# spi-breakout-v01.net
KiCad netlist of a schematic drawn in EAGLE
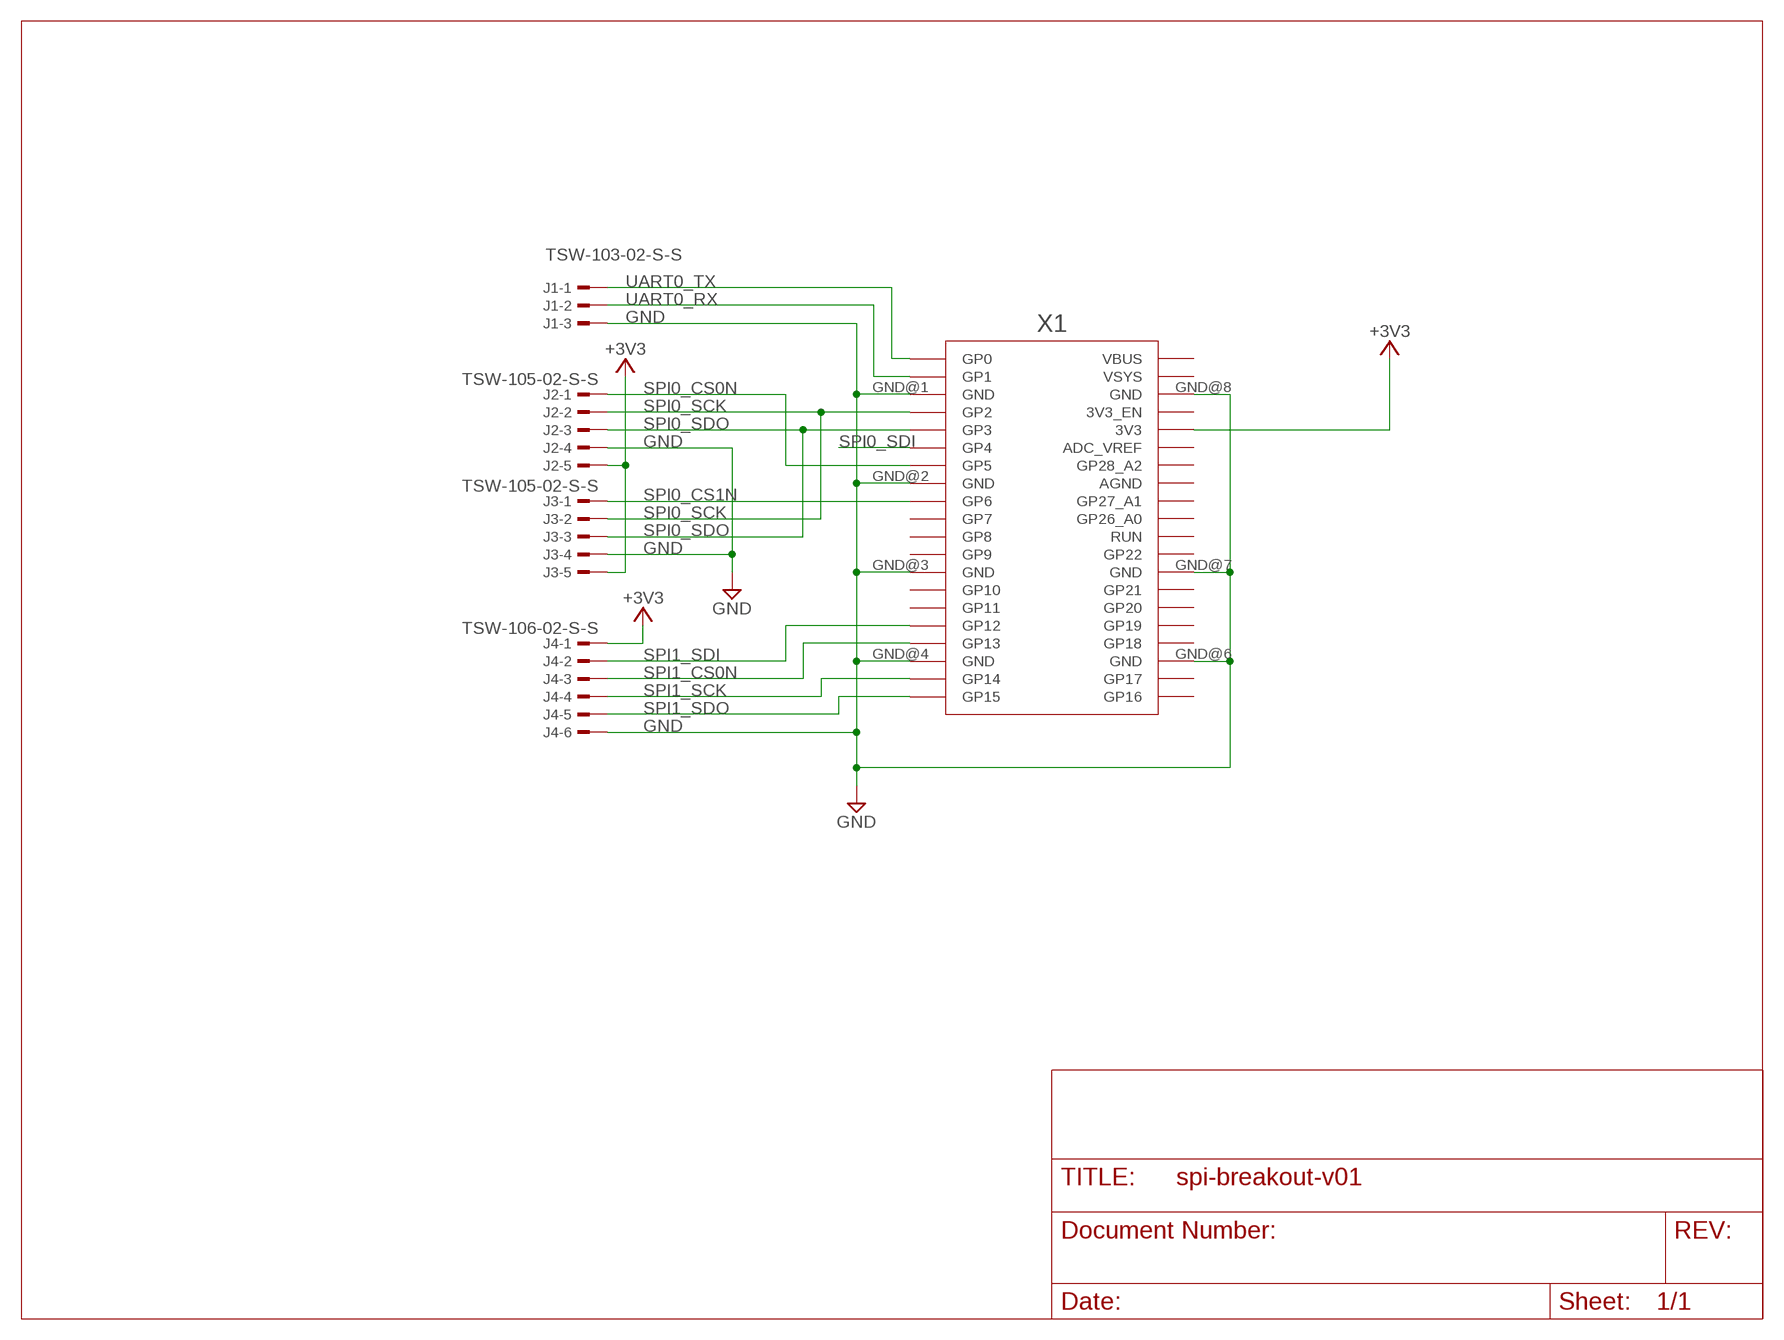
[diagram p0: schematic, sheet 1]

(export (version "E")
  (design (tool "Eeschema 10.0.6"))
  (components
    (comp (ref "J1")
      (value "TSW-103-02-S-S")
      (footprint "eagle-import:TSW-103-02-S-S")
      (libsource (lib "eagle-import") (part "TSW-103-02-S-S"))
    )
    (comp (ref "J2")
      (value "TSW-105-02-S-S")
      (footprint "eagle-import:TSW-105-02-S-S")
      (libsource (lib "eagle-import") (part "TSW-105-02-S-S"))
    )
    (comp (ref "J3")
      (value "TSW-105-02-S-S")
      (footprint "eagle-import:TSW-105-02-S-S")
      (libsource (lib "eagle-import") (part "TSW-105-02-S-S"))
    )
    (comp (ref "J4")
      (value "TSW-106-02-S-S")
      (footprint "eagle-import:TSW-106-02-S-S")
      (libsource (lib "eagle-import") (part "TSW-106-02-S-S"))
    )
    (comp (ref "X1")
      (value "RPI_PICO_IG-TH")
      (footprint "eagle-import:RPI_PICO_TH")
      (libsource (lib "eagle-import") (part "RPI_PICO_IG-TH"))
    )
  )
  (nets
    (net (code "1") (name "+3V3") (class "Default")
      (node (ref "J2") (pin "5") (pinfunction "1_5") (pintype "passive"))
      (node (ref "J3") (pin "5") (pinfunction "1_5") (pintype "passive"))
      (node (ref "J4") (pin "1") (pinfunction "1_1") (pintype "passive"))
      (node (ref "X1") (pin "3V3") (pinfunction "3V3_3V3") (pintype "bidirectional"))
    )
    (net (code "2") (name "/SPI0_CS0N") (class "Default")
      (node (ref "J2") (pin "1") (pinfunction "1_1") (pintype "passive"))
      (node (ref "X1") (pin "GP5") (pinfunction "GP5_GP5") (pintype "bidirectional"))
    )
    (net (code "3") (name "/SPI0_CS1N") (class "Default")
      (node (ref "J3") (pin "1") (pinfunction "1_1") (pintype "passive"))
      (node (ref "X1") (pin "GP6") (pinfunction "GP6_GP6") (pintype "bidirectional"))
    )
    (net (code "4") (name "/SPI0_SCK") (class "Default")
      (node (ref "J2") (pin "2") (pinfunction "1_2") (pintype "passive"))
      (node (ref "J3") (pin "2") (pinfunction "1_2") (pintype "passive"))
      (node (ref "X1") (pin "GP2") (pinfunction "GP2_GP2") (pintype "bidirectional"))
    )
    (net (code "5") (name "/SPI0_SDI") (class "Default")
      (node (ref "X1") (pin "GP4") (pinfunction "GP4_GP4") (pintype "bidirectional"))
    )
    (net (code "6") (name "/SPI0_SDO") (class "Default")
      (node (ref "J2") (pin "3") (pinfunction "1_3") (pintype "passive"))
      (node (ref "J3") (pin "3") (pinfunction "1_3") (pintype "passive"))
      (node (ref "X1") (pin "GP3") (pinfunction "GP3_GP3") (pintype "bidirectional"))
    )
    (net (code "7") (name "/SPI1_CS0N") (class "Default")
      (node (ref "J4") (pin "3") (pinfunction "1_3") (pintype "passive"))
      (node (ref "X1") (pin "GP13") (pinfunction "GP13_GP13") (pintype "bidirectional"))
    )
    (net (code "8") (name "/SPI1_SCK") (class "Default")
      (node (ref "J4") (pin "4") (pinfunction "1_4") (pintype "passive"))
      (node (ref "X1") (pin "GP14") (pinfunction "GP14_GP14") (pintype "bidirectional"))
    )
    (net (code "9") (name "/SPI1_SDI") (class "Default")
      (node (ref "J4") (pin "2") (pinfunction "1_2") (pintype "passive"))
      (node (ref "X1") (pin "GP12") (pinfunction "GP12_GP12") (pintype "bidirectional"))
    )
    (net (code "10") (name "/SPI1_SDO") (class "Default")
      (node (ref "J4") (pin "5") (pinfunction "1_5") (pintype "passive"))
      (node (ref "X1") (pin "GP15") (pinfunction "GP15_GP15") (pintype "bidirectional"))
    )
    (net (code "11") (name "/UART0_RX") (class "Default")
      (node (ref "J1") (pin "2") (pinfunction "1_2") (pintype "passive"))
      (node (ref "X1") (pin "GP1") (pinfunction "GP1_GP1") (pintype "bidirectional"))
    )
    (net (code "12") (name "/UART0_TX") (class "Default")
      (node (ref "J1") (pin "1") (pinfunction "1_1") (pintype "passive"))
      (node (ref "X1") (pin "GP0") (pinfunction "GP0_GP0") (pintype "bidirectional"))
    )
    (net (code "13") (name "GND") (class "Default")
      (node (ref "J1") (pin "3") (pinfunction "1_3") (pintype "passive"))
      (node (ref "J2") (pin "4") (pinfunction "1_4") (pintype "passive"))
      (node (ref "J3") (pin "4") (pinfunction "1_4") (pintype "passive"))
      (node (ref "J4") (pin "6") (pinfunction "1_6") (pintype "passive"))
      (node (ref "X1") (pin "GND@1") (pinfunction "GND_GND@1") (pintype "bidirectional"))
      (node (ref "X1") (pin "GND@2") (pinfunction "GND_GND@2") (pintype "bidirectional"))
      (node (ref "X1") (pin "GND@3") (pinfunction "GND_GND@3") (pintype "bidirectional"))
      (node (ref "X1") (pin "GND@4") (pinfunction "GND_GND@4") (pintype "bidirectional"))
      (node (ref "X1") (pin "GND@6") (pinfunction "GND_GND@6") (pintype "bidirectional"))
      (node (ref "X1") (pin "GND@7") (pinfunction "GND_GND@7") (pintype "bidirectional"))
      (node (ref "X1") (pin "GND@8") (pinfunction "GND_GND@8") (pintype "bidirectional"))
    )
    (net (code "14") (name "unconnected-(X1-Pad3V3_EN)") (class "Default")
      (node (ref "X1") (pin "3V3_EN") (pinfunction "3V3_EN_3V3_EN") (pintype "bidirectional"))
    )
    (net (code "15") (name "unconnected-(X1-PadADC_VREF)") (class "Default")
      (node (ref "X1") (pin "ADC_VREF") (pinfunction "ADC_VREF_ADC_VREF") (pintype "bidirectional"))
    )
    (net (code "16") (name "unconnected-(X1-PadAGND)") (class "Default")
      (node (ref "X1") (pin "AGND") (pinfunction "AGND_AGND") (pintype "bidirectional"))
    )
    (net (code "17") (name "unconnected-(X1-PadGP7)") (class "Default")
      (node (ref "X1") (pin "GP7") (pinfunction "GP7_GP7") (pintype "bidirectional"))
    )
    (net (code "18") (name "unconnected-(X1-PadGP8)") (class "Default")
      (node (ref "X1") (pin "GP8") (pinfunction "GP8_GP8") (pintype "bidirectional"))
    )
    (net (code "19") (name "unconnected-(X1-PadGP9)") (class "Default")
      (node (ref "X1") (pin "GP9") (pinfunction "GP9_GP9") (pintype "bidirectional"))
    )
    (net (code "20") (name "unconnected-(X1-PadGP10)") (class "Default")
      (node (ref "X1") (pin "GP10") (pinfunction "GP10_GP10") (pintype "bidirectional"))
    )
    (net (code "21") (name "unconnected-(X1-PadGP11)") (class "Default")
      (node (ref "X1") (pin "GP11") (pinfunction "GP11_GP11") (pintype "bidirectional"))
    )
    (net (code "22") (name "unconnected-(X1-PadGP16)") (class "Default")
      (node (ref "X1") (pin "GP16") (pinfunction "GP16_GP16") (pintype "bidirectional"))
    )
    (net (code "23") (name "unconnected-(X1-PadGP17)") (class "Default")
      (node (ref "X1") (pin "GP17") (pinfunction "GP17_GP17") (pintype "bidirectional"))
    )
    (net (code "24") (name "unconnected-(X1-PadGP18)") (class "Default")
      (node (ref "X1") (pin "GP18") (pinfunction "GP18_GP18") (pintype "bidirectional"))
    )
    (net (code "25") (name "unconnected-(X1-PadGP19)") (class "Default")
      (node (ref "X1") (pin "GP19") (pinfunction "GP19_GP19") (pintype "bidirectional"))
    )
    (net (code "26") (name "unconnected-(X1-PadGP20)") (class "Default")
      (node (ref "X1") (pin "GP20") (pinfunction "GP20_GP20") (pintype "bidirectional"))
    )
    (net (code "27") (name "unconnected-(X1-PadGP21)") (class "Default")
      (node (ref "X1") (pin "GP21") (pinfunction "GP21_GP21") (pintype "bidirectional"))
    )
    (net (code "28") (name "unconnected-(X1-PadGP22)") (class "Default")
      (node (ref "X1") (pin "GP22") (pinfunction "GP22_GP22") (pintype "bidirectional"))
    )
    (net (code "29") (name "unconnected-(X1-PadGP26_A0)") (class "Default")
      (node (ref "X1") (pin "GP26_A0") (pinfunction "GP26_A0_GP26_A0") (pintype "bidirectional"))
    )
    (net (code "30") (name "unconnected-(X1-PadGP27_A1)") (class "Default")
      (node (ref "X1") (pin "GP27_A1") (pinfunction "GP27_A1_GP27_A1") (pintype "bidirectional"))
    )
    (net (code "31") (name "unconnected-(X1-PadGP28_A2)") (class "Default")
      (node (ref "X1") (pin "GP28_A2") (pinfunction "GP28_A2_GP28_A2") (pintype "bidirectional"))
    )
    (net (code "32") (name "unconnected-(X1-PadRUN)") (class "Default")
      (node (ref "X1") (pin "RUN") (pinfunction "RUN_RUN") (pintype "bidirectional"))
    )
    (net (code "33") (name "unconnected-(X1-PadVBUS)") (class "Default")
      (node (ref "X1") (pin "VBUS") (pinfunction "VBUS_VBUS") (pintype "bidirectional"))
    )
    (net (code "34") (name "unconnected-(X1-PadVSYS)") (class "Default")
      (node (ref "X1") (pin "VSYS") (pinfunction "VSYS_VSYS") (pintype "bidirectional"))
    )
  )
)
